# SD.net
KiCad netlist of a schematic drawn in Altium Designer
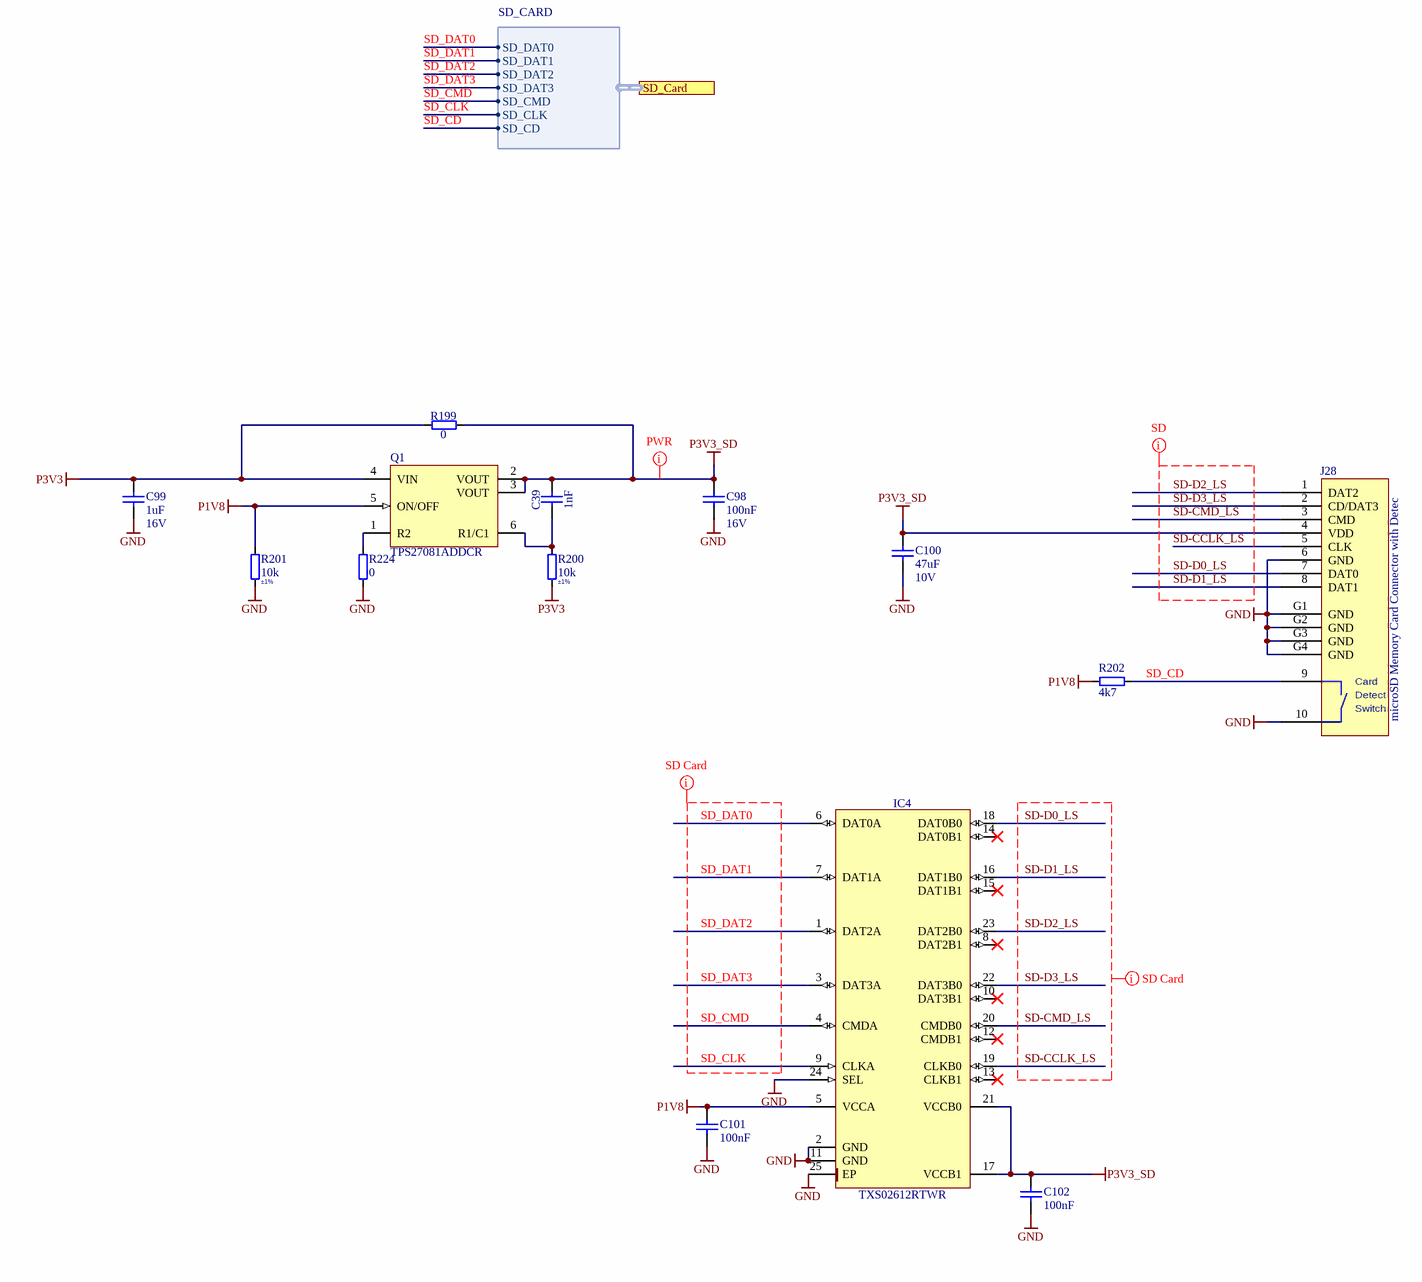
[diagram p0: SD.SchDoc]

(export (version "E")
  (design (tool "Eeschema 10.0.6"))
  (components
    (comp (ref "C39")
      (value "1nF")
      (footprint "CAPC1005X55N")
      (description "Non-polarised capacitor")
      (fields
        (field (name "PART NUMBER") "CC0402_1NF_50V_10%_X7R")
        (field (name "VOLTAGE") "50V")
        (field (name "AUTHOR") "CERN DEM JLC")
      )
      (libsource (lib "Capacitors") (part "Capacitor - non polarized"))
    )
    (comp (ref "C98")
      (value "100nF")
      (footprint "CAPC1005X55N")
      (description "Non-polarised capacitor")
      (fields
        (field (name "VOLTAGE") "16V")
        (field (name "PART NUMBER") "CC0402_100NF_16V_10%_X7R")
        (field (name "TOLERANCE") "±10%")
        (field (name "AUTHOR") "CERN DEM JLC")
      )
      (libsource (lib "Capacitors") (part "Capacitor - non polarized"))
    )
    (comp (ref "C99")
      (value "1uF")
      (footprint "CAPC1005X55N")
      (description "Non-polarised capacitor")
      (fields
        (field (name "VOLTAGE") "16V")
        (field (name "TOLERANCE") "±10%")
        (field (name "PART NUMBER") "CC0402_1UF_16V_10%_X5R")
        (field (name "AUTHOR") "CERN DEM JLC")
      )
      (libsource (lib "Capacitors") (part "Capacitor - non polarized"))
    )
    (comp (ref "C100")
      (value "47uF")
      (footprint "CAPC3216X180N")
      (description "Non-polarised capacitor")
      (fields
        (field (name "VOLTAGE") "10V")
        (field (name "TOLERANCE") "±10%")
        (field (name "PART NUMBER") "CC1206_47UF_10V_10%_X5R")
        (field (name "AUTHOR") "CERN DEM MR")
      )
      (libsource (lib "Capacitors") (part "Capacitor - non polarized"))
    )
    (comp (ref "C101")
      (value "100nF")
      (footprint "CAPC1005X55N")
      (description "Non-polarised capacitor")
      (fields
        (field (name "VOLTAGE") "16V")
        (field (name "PART NUMBER") "CC0402_100NF_16V_10%_X7R")
        (field (name "AUTHOR") "CERN DEM JLC")
      )
      (libsource (lib "Capacitors") (part "Capacitor - non polarized"))
    )
    (comp (ref "C102")
      (value "100nF")
      (footprint "CAPC1005X55N")
      (description "Non-polarised capacitor")
      (fields
        (field (name "VOLTAGE") "16V")
        (field (name "PART NUMBER") "CC0402_100NF_16V_10%_X7R")
        (field (name "AUTHOR") "CERN DEM JLC")
      )
      (libsource (lib "Capacitors") (part "Capacitor - non polarized"))
    )
    (comp (ref "IC4")
      (value "TXS02612RTWR")
      (footprint "QFN50P400X400X80-25N-S255")
      (description "SDIO Port Expander With Voltage-Level Translation")
      (fields (field (name "MANUFACTURER") "TEXAS INSTRUMENTS") (field (name "AUTHOR") "CERN DEM JLC"))
      (libsource (lib "ICs And Semiconductors") (part "TXS02612RTWR"))
    )
    (comp (ref "J28")
      (value "microSD Memory Card Connector with Detec")
      (footprint "104031-0811")
      (description "microSD Memory Card Connector with Detect Switch")
      (fields (field (name "MANUFACTURER PART NUMBER") "Molex 104031-0811"))
      (libsource (lib "TE") (part "104031-0811"))
    )
    (comp (ref "Q1")
      (value "TPS27081ADDCR")
      (footprint "SOT95P280X110-6N")
      (libsource (lib "TE") (part "TPS27081A"))
    )
    (comp (ref "R199")
      (value "0")
      (footprint "RESC2012X60N")
      (description "Resistor")
      (fields
        (field (name "PART NUMBER") "R0805_0R_JUMPER")
        (field (name "MANUFACTURER") "GENERIC")
        (field (name "AUTHOR") "CERN DEM JLC")
      )
      (libsource (lib "Resistors") (part "Resistor"))
    )
    (comp (ref "R200")
      (value "10k")
      (footprint "RESC1005X40N")
      (description "Resistor - 1%")
      (fields
        (field (name "TOLERANCE") "±1%")
        (field (name "PART NUMBER") "R0402_10K_1%_0.0625W_100PPM")
        (field (name "POWER") "0.0625W")
        (field (name "AUTHOR") "CERN DEM JLC")
      )
      (libsource (lib "Resistors") (part "Resistor - 1%"))
    )
    (comp (ref "R201")
      (value "10k")
      (footprint "RESC1005X40N")
      (description "Resistor - 1%")
      (fields
        (field (name "TOLERANCE") "±1%")
        (field (name "PART NUMBER") "R0402_10K_1%_0.0625W_100PPM")
        (field (name "POWER") "0.0625W")
        (field (name "AUTHOR") "CERN DEM JLC")
      )
      (libsource (lib "Resistors") (part "Resistor - 1%"))
    )
    (comp (ref "R202")
      (value "4k7")
      (footprint "RESC1005X40N")
      (description "Resistor - 1%")
      (fields
        (field (name "TOLERANCE") "±1%")
        (field (name "PART NUMBER") "R0402_4K7_1%_0.0625W_100PPM")
        (field (name "AUTHOR") "CERN DEM JLC")
      )
      (libsource (lib "Resistors") (part "Resistor - 1%"))
    )
    (comp (ref "R224")
      (value "0")
      (footprint "RESC1005X40N")
      (description "Resistor")
      (fields
        (field (name "PART NUMBER") "R0402_0R_JUMPER")
        (field (name "MANUFACTURER") "GENERIC")
        (field (name "AUTHOR") "CERN DEM JLC")
      )
      (libsource (lib "Resistors") (part "Resistor"))
    )
  )
  (nets
    (net (code "2") (name "/SD-CCLK_LS") (class "Default")
      (node (ref "IC4") (pin "19") (pinfunction "CLKB0_19") (pintype "bidirectional"))
      (node (ref "J28") (pin "5") (pinfunction "CLK_5") (pintype "passive"))
    )
    (net (code "3") (name "/SD-CMD_LS") (class "Default")
      (node (ref "IC4") (pin "20") (pinfunction "CMDB0_20") (pintype "bidirectional"))
      (node (ref "J28") (pin "3") (pinfunction "CMD_3") (pintype "passive"))
    )
    (net (code "4") (name "/SD-D0_LS") (class "Default")
      (node (ref "IC4") (pin "18") (pinfunction "DAT0B0_18") (pintype "bidirectional"))
      (node (ref "J28") (pin "7") (pinfunction "DAT0_7") (pintype "passive"))
    )
    (net (code "5") (name "/SD-D1_LS") (class "Default")
      (node (ref "IC4") (pin "16") (pinfunction "DAT1B0_16") (pintype "bidirectional"))
      (node (ref "J28") (pin "8") (pinfunction "DAT1_8") (pintype "passive"))
    )
    (net (code "6") (name "/SD-D2_LS") (class "Default")
      (node (ref "IC4") (pin "23") (pinfunction "DAT2B0_23") (pintype "bidirectional"))
      (node (ref "J28") (pin "1") (pinfunction "DAT2_1") (pintype "passive"))
    )
    (net (code "7") (name "/SD-D3_LS") (class "Default")
      (node (ref "IC4") (pin "22") (pinfunction "DAT3B0_22") (pintype "bidirectional"))
      (node (ref "J28") (pin "2") (pinfunction "CD/DAT3_2") (pintype "passive"))
    )
    (net (code "8") (name "/SD_CD") (class "Default")
      (node (ref "J28") (pin "9") (pinfunction "CDSW_9") (pintype "passive"))
      (node (ref "R202") (pin "1") (pinfunction "1_1") (pintype "passive"))
    )
    (net (code "9") (name "/SD_CLK") (class "Default")
      (node (ref "IC4") (pin "9") (pinfunction "CLKA_9") (pintype "input"))
    )
    (net (code "10") (name "/SD_CMD") (class "Default")
      (node (ref "IC4") (pin "4") (pinfunction "CMDA_4") (pintype "bidirectional"))
    )
    (net (code "11") (name "/SD_DAT0") (class "Default")
      (node (ref "IC4") (pin "6") (pinfunction "DAT0A_6") (pintype "bidirectional"))
    )
    (net (code "12") (name "/SD_DAT1") (class "Default")
      (node (ref "IC4") (pin "7") (pinfunction "DAT1A_7") (pintype "bidirectional"))
    )
    (net (code "13") (name "/SD_DAT2") (class "Default")
      (node (ref "IC4") (pin "1") (pinfunction "DAT2A_1") (pintype "bidirectional"))
    )
    (net (code "14") (name "/SD_DAT3") (class "Default")
      (node (ref "IC4") (pin "3") (pinfunction "DAT3A_3") (pintype "bidirectional"))
    )
    (net (code "16") (name "GND") (class "Default")
      (node (ref "C100") (pin "1") (pinfunction "1_1") (pintype "passive"))
      (node (ref "C101") (pin "2") (pinfunction "2_2") (pintype "passive"))
      (node (ref "C102") (pin "2") (pinfunction "2_2") (pintype "passive"))
      (node (ref "C98") (pin "1") (pinfunction "1_1") (pintype "passive"))
      (node (ref "C99") (pin "2") (pinfunction "2_2") (pintype "passive"))
      (node (ref "IC4") (pin "11") (pinfunction "GND_11") (pintype "power_in"))
      (node (ref "IC4") (pin "2") (pinfunction "GND_2") (pintype "power_in"))
      (node (ref "IC4") (pin "24") (pinfunction "SEL_24") (pintype "input"))
      (node (ref "IC4") (pin "25") (pinfunction "EP_25") (pintype "power_in"))
      (node (ref "J28") (pin "10") (pinfunction "CDSW_10") (pintype "passive"))
      (node (ref "J28") (pin "6") (pinfunction "GND_6") (pintype "passive"))
      (node (ref "J28") (pin "G1") (pinfunction "GND_G1") (pintype "passive"))
      (node (ref "J28") (pin "G2") (pinfunction "GND_G2") (pintype "passive"))
      (node (ref "J28") (pin "G3") (pinfunction "GND_G3") (pintype "passive"))
      (node (ref "J28") (pin "G4") (pinfunction "GND_G4") (pintype "passive"))
      (node (ref "R201") (pin "2") (pinfunction "2_2") (pintype "passive"))
      (node (ref "R224") (pin "2") (pinfunction "2_2") (pintype "passive"))
    )
    (net (code "17") (name "Net-(Q1-R1{slash}C1)") (class "Default")
      (node (ref "C39") (pin "1") (pinfunction "1_1") (pintype "passive"))
      (node (ref "Q1") (pin "6") (pinfunction "R1/C1_6") (pintype "power_in"))
      (node (ref "R200") (pin "1") (pinfunction "1_1") (pintype "passive"))
    )
    (net (code "18") (name "Net-(Q1-R2)") (class "Default")
      (node (ref "Q1") (pin "1") (pinfunction "R2_1") (pintype "power_in"))
      (node (ref "R224") (pin "1") (pinfunction "1_1") (pintype "passive"))
    )
    (net (code "19") (name "P1V8") (class "Default")
      (node (ref "C101") (pin "1") (pinfunction "1_1") (pintype "passive"))
      (node (ref "IC4") (pin "5") (pinfunction "VCCA_5") (pintype "power_in"))
      (node (ref "Q1") (pin "5") (pinfunction "ON/OFF_5") (pintype "input"))
      (node (ref "R201") (pin "1") (pinfunction "1_1") (pintype "passive"))
      (node (ref "R202") (pin "2") (pinfunction "2_2") (pintype "passive"))
    )
    (net (code "20") (name "P3V3") (class "Default")
      (node (ref "C99") (pin "1") (pinfunction "1_1") (pintype "passive"))
      (node (ref "Q1") (pin "4") (pinfunction "VIN_4") (pintype "power_in"))
      (node (ref "R199") (pin "1") (pinfunction "1_1") (pintype "passive"))
      (node (ref "R200") (pin "2") (pinfunction "2_2") (pintype "passive"))
    )
    (net (code "21") (name "P3V3_SD") (class "Default")
      (node (ref "C100") (pin "2") (pinfunction "2_2") (pintype "passive"))
      (node (ref "C102") (pin "1") (pinfunction "1_1") (pintype "passive"))
      (node (ref "C39") (pin "2") (pinfunction "2_2") (pintype "passive"))
      (node (ref "C98") (pin "2") (pinfunction "2_2") (pintype "passive"))
      (node (ref "IC4") (pin "17") (pinfunction "VCCB1_17") (pintype "power_in"))
      (node (ref "IC4") (pin "21") (pinfunction "VCCB0_21") (pintype "power_in"))
      (node (ref "J28") (pin "4") (pinfunction "VDD_4") (pintype "passive"))
      (node (ref "Q1") (pin "2") (pinfunction "VOUT_2") (pintype "power_in"))
      (node (ref "Q1") (pin "3") (pinfunction "VOUT_3") (pintype "power_in"))
      (node (ref "R199") (pin "2") (pinfunction "2_2") (pintype "passive"))
    )
    (net (code "22") (name "unconnected-(IC4-CLKB1-Pad13)") (class "Default")
      (node (ref "IC4") (pin "13") (pinfunction "CLKB1_13") (pintype "bidirectional+no_connect"))
    )
    (net (code "23") (name "unconnected-(IC4-CMDB1-Pad12)") (class "Default")
      (node (ref "IC4") (pin "12") (pinfunction "CMDB1_12") (pintype "bidirectional+no_connect"))
    )
    (net (code "24") (name "unconnected-(IC4-DAT0B1-Pad14)") (class "Default")
      (node (ref "IC4") (pin "14") (pinfunction "DAT0B1_14") (pintype "bidirectional+no_connect"))
    )
    (net (code "25") (name "unconnected-(IC4-DAT1B1-Pad15)") (class "Default")
      (node (ref "IC4") (pin "15") (pinfunction "DAT1B1_15") (pintype "bidirectional+no_connect"))
    )
    (net (code "26") (name "unconnected-(IC4-DAT2B1-Pad8)") (class "Default")
      (node (ref "IC4") (pin "8") (pinfunction "DAT2B1_8") (pintype "bidirectional+no_connect"))
    )
    (net (code "27") (name "unconnected-(IC4-DAT3B1-Pad10)") (class "Default")
      (node (ref "IC4") (pin "10") (pinfunction "DAT3B1_10") (pintype "bidirectional+no_connect"))
    )
  )
)
